# LEDController.net
KiCad netlist of a schematic drawn in EAGLE
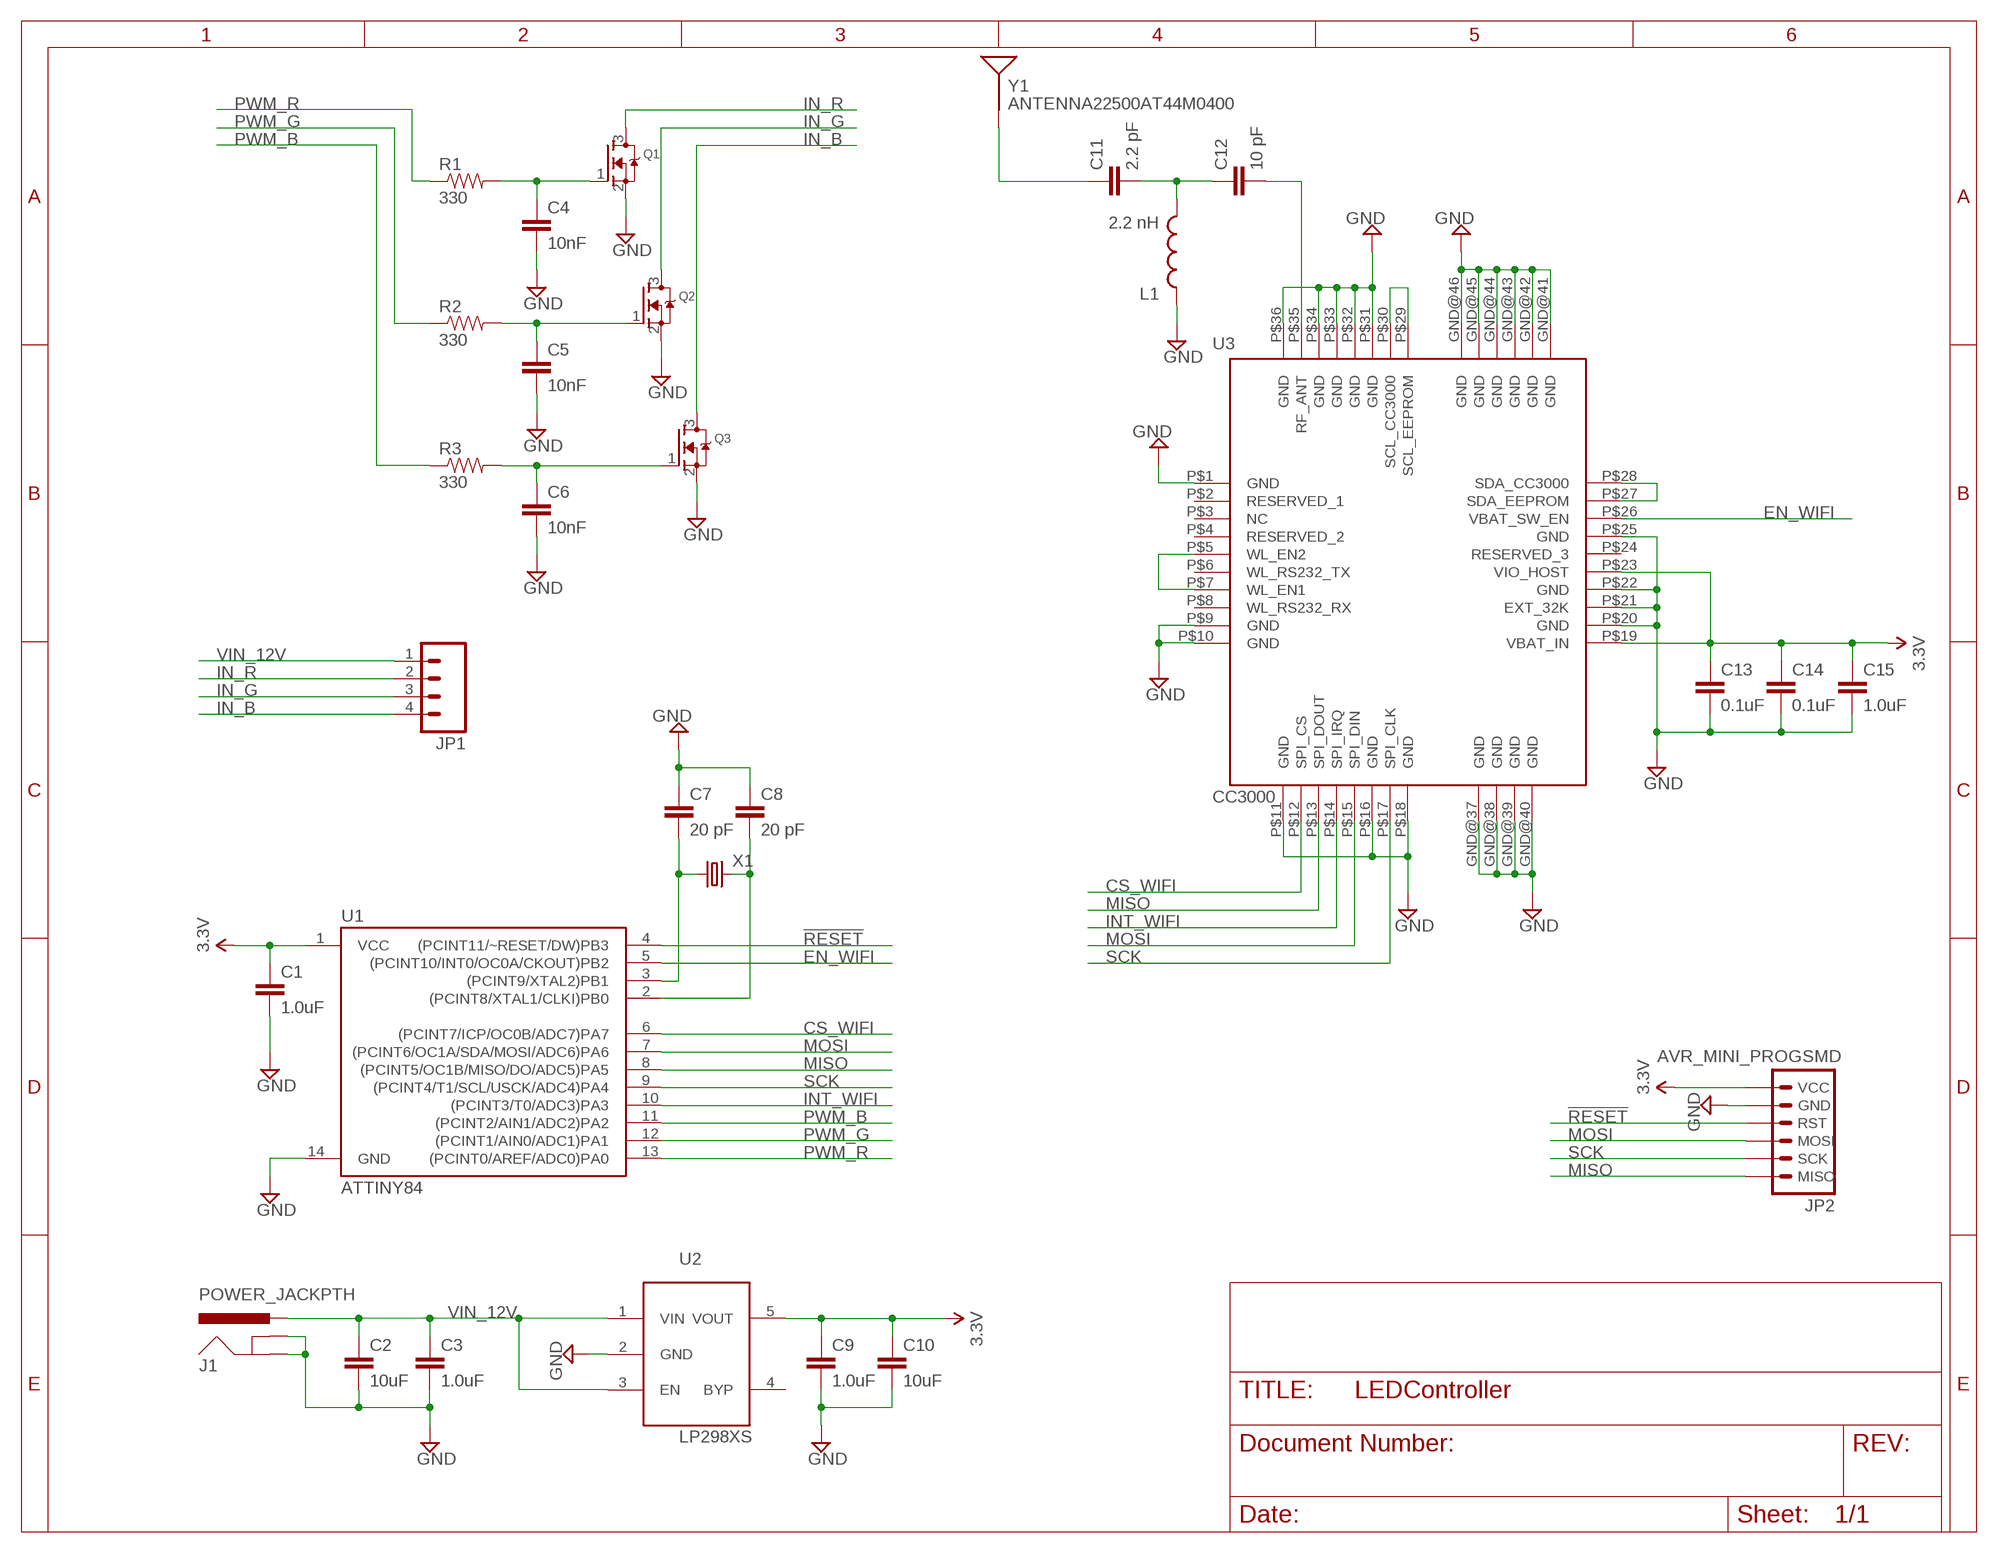
[diagram p0: schematic, sheet 1]

(export (version "E")
  (design (tool "Eeschema 10.0.6"))
  (components
    (comp (ref "C1")
      (value "1.0uF")
      (footprint "eagle-import:0603-CAP")
      (libsource (lib "eagle-import") (part "1.0UF-16V-10%(0603)"))
    )
    (comp (ref "C2")
      (value "10uF")
      (footprint "eagle-import:0603-CAP")
      (libsource (lib "eagle-import") (part "10UF-6.3V-20%(0603)"))
    )
    (comp (ref "C3")
      (value "1.0uF")
      (footprint "eagle-import:0603-CAP")
      (libsource (lib "eagle-import") (part "1.0UF-16V-10%(0603)"))
    )
    (comp (ref "C4")
      (value "10nF")
      (footprint "eagle-import:0603-CAP")
      (libsource (lib "eagle-import") (part "10NF/10000PF-50V-10%(0603)"))
    )
    (comp (ref "C5")
      (value "10nF")
      (footprint "eagle-import:0603-CAP")
      (libsource (lib "eagle-import") (part "10NF/10000PF-50V-10%(0603)"))
    )
    (comp (ref "C6")
      (value "10nF")
      (footprint "eagle-import:0603-CAP")
      (libsource (lib "eagle-import") (part "10NF/10000PF-50V-10%(0603)"))
    )
    (comp (ref "C7")
      (value "20 pF")
      (footprint "eagle-import:0603-CAP")
      (libsource (lib "eagle-import") (part "9.0PF-50V-10%(0603)"))
    )
    (comp (ref "C8")
      (value "20 pF")
      (footprint "eagle-import:0603-CAP")
      (libsource (lib "eagle-import") (part "9.0PF-50V-10%(0603)"))
    )
    (comp (ref "C9")
      (value "1.0uF")
      (footprint "eagle-import:0603-CAP")
      (libsource (lib "eagle-import") (part "1.0UF-16V-10%(0603)"))
    )
    (comp (ref "C10")
      (value "10uF")
      (footprint "eagle-import:0603-CAP")
      (libsource (lib "eagle-import") (part "10UF-6.3V-20%(0603)"))
    )
    (comp (ref "C11")
      (value "2.2 pF")
      (footprint "eagle-import:0603-CAP")
      (libsource (lib "eagle-import") (part "9.0PF-50V-10%(0603)"))
    )
    (comp (ref "C12")
      (value "10 pF")
      (footprint "eagle-import:0603-CAP")
      (libsource (lib "eagle-import") (part "9.0PF-50V-10%(0603)"))
    )
    (comp (ref "C13")
      (value "0.1uF")
      (footprint "eagle-import:0603-CAP")
      (libsource (lib "eagle-import") (part "0.1UF-25V-5%(0603)"))
    )
    (comp (ref "C14")
      (value "0.1uF")
      (footprint "eagle-import:0603-CAP")
      (libsource (lib "eagle-import") (part "0.1UF-25V-5%(0603)"))
    )
    (comp (ref "C15")
      (value "1.0uF")
      (footprint "eagle-import:0603-CAP")
      (libsource (lib "eagle-import") (part "1.0UF-16V-10%(0603)"))
    )
    (comp (ref "J1")
      (value "POWER_JACKPTH")
      (footprint "eagle-import:POWER_JACK_PTH")
      (libsource (lib "eagle-import") (part "POWER_JACKPTH"))
    )
    (comp (ref "JP1")
      (value "M04PTH")
      (footprint "eagle-import:1X04")
      (libsource (lib "eagle-import") (part "M04PTH"))
    )
    (comp (ref "JP2")
      (value "AVR_MINI_PROGSMD")
      (footprint "eagle-import:AVR_MINI_PROG")
      (libsource (lib "eagle-import") (part "AVR_MINI_PROGSMD"))
    )
    (comp (ref "L1")
      (value "2.2 nH")
      (footprint "eagle-import:0603")
      (libsource (lib "eagle-import") (part "INDUCTOR0603"))
    )
    (comp (ref "Q1")
      (value "MOSFET-NREFLOW")
      (footprint "eagle-import:SOT23")
      (libsource (lib "eagle-import") (part "MOSFET-NREFLOW"))
    )
    (comp (ref "Q2")
      (value "MOSFET-NREFLOW")
      (footprint "eagle-import:SOT23")
      (libsource (lib "eagle-import") (part "MOSFET-NREFLOW"))
    )
    (comp (ref "Q3")
      (value "MOSFET-NREFLOW")
      (footprint "eagle-import:SOT23")
      (libsource (lib "eagle-import") (part "MOSFET-NREFLOW"))
    )
    (comp (ref "R1")
      (value "330")
      (footprint "eagle-import:0603-RES")
      (libsource (lib "eagle-import") (part "330OHM1/10W1%(0603)"))
    )
    (comp (ref "R2")
      (value "330")
      (footprint "eagle-import:0603-RES")
      (libsource (lib "eagle-import") (part "330OHM1/10W1%(0603)"))
    )
    (comp (ref "R3")
      (value "330")
      (footprint "eagle-import:0603-RES")
      (libsource (lib "eagle-import") (part "330OHM1/10W1%(0603)"))
    )
    (comp (ref "U1")
      (value "ATTINY84")
      (footprint "eagle-import:SO14")
      (libsource (lib "eagle-import") (part "ATTINY84"))
    )
    (comp (ref "U2")
      (value "LP298XS")
      (footprint "eagle-import:SOT23-5L")
      (libsource (lib "eagle-import") (part "LP298XS"))
    )
    (comp (ref "U3")
      (value "CC3000")
      (footprint "eagle-import:QFN-46_CC3000")
      (libsource (lib "eagle-import") (part "CC3000"))
    )
    (comp (ref "X1")
      (value "CRYSTAL5X3")
      (footprint "eagle-import:CRYSTAL-SMD-5X3")
      (libsource (lib "eagle-import") (part "CRYSTAL5X3"))
    )
    (comp (ref "Y1")
      (value "ANTENNA22500AT44M0400")
      (footprint "eagle-import:ANTENNA-CHIP_2500AT44M0400")
      (libsource (lib "eagle-import") (part "ANTENNA22500AT44M0400"))
    )
  )
  (nets
    (net (code "1") (name "/CS_WIFI") (class "Default")
      (node (ref "U1") (pin "6") (pinfunction "(PCINT7/ICP/OC0B/ADC7)PA7_6") (pintype "bidirectional"))
      (node (ref "U3") (pin "P$12") (pinfunction "SPI_CS_P$12") (pintype "bidirectional"))
    )
    (net (code "2") (name "/EN_WIFI") (class "Default")
      (node (ref "U1") (pin "5") (pinfunction "(PCINT10/INT0/OC0A/CKOUT)PB2_5") (pintype "bidirectional"))
      (node (ref "U3") (pin "P$26") (pinfunction "VBAT_SW_EN_P$26") (pintype "bidirectional"))
    )
    (net (code "3") (name "/INT_WIFI") (class "Default")
      (node (ref "U1") (pin "10") (pinfunction "(PCINT3/T0/ADC3)PA3_10") (pintype "bidirectional"))
      (node (ref "U3") (pin "P$14") (pinfunction "SPI_IRQ_P$14") (pintype "bidirectional"))
    )
    (net (code "4") (name "/IN_B") (class "Default")
      (node (ref "JP1") (pin "4") (pinfunction "4_4") (pintype "passive"))
      (node (ref "Q3") (pin "3") (pinfunction "D_3") (pintype "bidirectional"))
    )
    (net (code "5") (name "/IN_G") (class "Default")
      (node (ref "JP1") (pin "3") (pinfunction "3_3") (pintype "passive"))
      (node (ref "Q2") (pin "3") (pinfunction "D_3") (pintype "bidirectional"))
    )
    (net (code "6") (name "/IN_R") (class "Default")
      (node (ref "JP1") (pin "2") (pinfunction "2_2") (pintype "passive"))
      (node (ref "Q1") (pin "3") (pinfunction "D_3") (pintype "bidirectional"))
    )
    (net (code "7") (name "/MISO") (class "Default")
      (node (ref "JP2") (pin "6") (pinfunction "MISO_6") (pintype "passive"))
      (node (ref "U1") (pin "8") (pinfunction "(PCINT5/OC1B/MISO/DO/ADC5)PA5_8") (pintype "bidirectional"))
      (node (ref "U3") (pin "P$13") (pinfunction "SPI_DOUT_P$13") (pintype "bidirectional"))
    )
    (net (code "8") (name "/MOSI") (class "Default")
      (node (ref "JP2") (pin "4") (pinfunction "MOSI_4") (pintype "passive"))
      (node (ref "U1") (pin "7") (pinfunction "(PCINT6/OC1A/SDA/MOSI/ADC6)PA6_7") (pintype "bidirectional"))
      (node (ref "U3") (pin "P$15") (pinfunction "SPI_DIN_P$15") (pintype "bidirectional"))
    )
    (net (code "9") (name "/PWM_B") (class "Default")
      (node (ref "R3") (pin "1") (pinfunction "1_1") (pintype "passive"))
      (node (ref "U1") (pin "11") (pinfunction "(PCINT2/AIN1/ADC2)PA2_11") (pintype "bidirectional"))
    )
    (net (code "10") (name "/PWM_G") (class "Default")
      (node (ref "R2") (pin "1") (pinfunction "1_1") (pintype "passive"))
      (node (ref "U1") (pin "12") (pinfunction "(PCINT1/AIN0/ADC1)PA1_12") (pintype "bidirectional"))
    )
    (net (code "11") (name "/PWM_R") (class "Default")
      (node (ref "R1") (pin "1") (pinfunction "1_1") (pintype "passive"))
      (node (ref "U1") (pin "13") (pinfunction "(PCINT0/AREF/ADC0)PA0_13") (pintype "bidirectional"))
    )
    (net (code "12") (name "/SCK") (class "Default")
      (node (ref "JP2") (pin "5") (pinfunction "SCK_5") (pintype "passive"))
      (node (ref "U1") (pin "9") (pinfunction "(PCINT4/T1/SCL/USCK/ADC4)PA4_9") (pintype "bidirectional"))
      (node (ref "U3") (pin "P$17") (pinfunction "SPI_CLK_P$17") (pintype "bidirectional"))
    )
    (net (code "13") (name "/VIN_12V") (class "Default")
      (node (ref "C2") (pin "1") (pinfunction "1_1") (pintype "passive"))
      (node (ref "C3") (pin "1") (pinfunction "1_1") (pintype "passive"))
      (node (ref "J1") (pin "PWR") (pinfunction "PWR_PWR") (pintype "bidirectional"))
      (node (ref "JP1") (pin "1") (pinfunction "1_1") (pintype "passive"))
      (node (ref "U2") (pin "1") (pinfunction "VIN_1") (pintype "bidirectional"))
      (node (ref "U2") (pin "3") (pinfunction "EN_3") (pintype "bidirectional"))
    )
    (net (code "14") (name "/~{RESET}") (class "Default")
      (node (ref "JP2") (pin "3") (pinfunction "RST_3") (pintype "passive"))
      (node (ref "U1") (pin "4") (pinfunction "(PCINT11/~{RESET/DW})PB3_4") (pintype "bidirectional"))
    )
    (net (code "15") (name "3.3V") (class "Default")
      (node (ref "C1") (pin "1") (pinfunction "1_1") (pintype "passive"))
      (node (ref "C10") (pin "1") (pinfunction "1_1") (pintype "passive"))
      (node (ref "C13") (pin "1") (pinfunction "1_1") (pintype "passive"))
      (node (ref "C14") (pin "1") (pinfunction "1_1") (pintype "passive"))
      (node (ref "C15") (pin "1") (pinfunction "1_1") (pintype "passive"))
      (node (ref "C9") (pin "1") (pinfunction "1_1") (pintype "passive"))
      (node (ref "JP2") (pin "1") (pinfunction "VCC_1") (pintype "passive"))
      (node (ref "U1") (pin "1") (pinfunction "VCC_1") (pintype "bidirectional"))
      (node (ref "U2") (pin "5") (pinfunction "VOUT_5") (pintype "bidirectional"))
      (node (ref "U3") (pin "P$19") (pinfunction "VBAT_IN_P$19") (pintype "bidirectional"))
      (node (ref "U3") (pin "P$23") (pinfunction "VIO_HOST_P$23") (pintype "bidirectional"))
    )
    (net (code "16") (name "GND") (class "Default")
      (node (ref "C1") (pin "2") (pinfunction "2_2") (pintype "passive"))
      (node (ref "C10") (pin "2") (pinfunction "2_2") (pintype "passive"))
      (node (ref "C13") (pin "2") (pinfunction "2_2") (pintype "passive"))
      (node (ref "C14") (pin "2") (pinfunction "2_2") (pintype "passive"))
      (node (ref "C15") (pin "2") (pinfunction "2_2") (pintype "passive"))
      (node (ref "C2") (pin "2") (pinfunction "2_2") (pintype "passive"))
      (node (ref "C3") (pin "2") (pinfunction "2_2") (pintype "passive"))
      (node (ref "C4") (pin "2") (pinfunction "2_2") (pintype "passive"))
      (node (ref "C5") (pin "2") (pinfunction "2_2") (pintype "passive"))
      (node (ref "C6") (pin "2") (pinfunction "2_2") (pintype "passive"))
      (node (ref "C7") (pin "1") (pinfunction "1_1") (pintype "passive"))
      (node (ref "C8") (pin "1") (pinfunction "1_1") (pintype "passive"))
      (node (ref "C9") (pin "2") (pinfunction "2_2") (pintype "passive"))
      (node (ref "J1") (pin "GND") (pinfunction "GND_GND") (pintype "bidirectional"))
      (node (ref "J1") (pin "GNDBREAK") (pinfunction "GNDBREAK_GNDBREAK") (pintype "bidirectional"))
      (node (ref "JP2") (pin "2") (pinfunction "GND_2") (pintype "passive"))
      (node (ref "L1") (pin "1") (pinfunction "1_1") (pintype "passive"))
      (node (ref "Q1") (pin "2") (pinfunction "S_2") (pintype "bidirectional"))
      (node (ref "Q2") (pin "2") (pinfunction "S_2") (pintype "bidirectional"))
      (node (ref "Q3") (pin "2") (pinfunction "S_2") (pintype "bidirectional"))
      (node (ref "U1") (pin "14") (pinfunction "GND_14") (pintype "bidirectional"))
      (node (ref "U2") (pin "2") (pinfunction "GND_2") (pintype "bidirectional"))
      (node (ref "U3") (pin "GND@37") (pinfunction "GND_GND@37") (pintype "bidirectional"))
      (node (ref "U3") (pin "GND@38") (pinfunction "GND_GND@38") (pintype "bidirectional"))
      (node (ref "U3") (pin "GND@39") (pinfunction "GND_GND@39") (pintype "bidirectional"))
      (node (ref "U3") (pin "GND@40") (pinfunction "GND_GND@40") (pintype "bidirectional"))
      (node (ref "U3") (pin "GND@41") (pinfunction "GND_GND@41") (pintype "bidirectional"))
      (node (ref "U3") (pin "GND@42") (pinfunction "GND_GND@42") (pintype "bidirectional"))
      (node (ref "U3") (pin "GND@43") (pinfunction "GND_GND@43") (pintype "bidirectional"))
      (node (ref "U3") (pin "GND@44") (pinfunction "GND_GND@44") (pintype "bidirectional"))
      (node (ref "U3") (pin "GND@45") (pinfunction "GND_GND@45") (pintype "bidirectional"))
      (node (ref "U3") (pin "GND@46") (pinfunction "GND_GND@46") (pintype "bidirectional"))
      (node (ref "U3") (pin "P$1") (pinfunction "GND_P$1") (pintype "bidirectional"))
      (node (ref "U3") (pin "P$10") (pinfunction "GND_P$10") (pintype "bidirectional"))
      (node (ref "U3") (pin "P$11") (pinfunction "GND_P$11") (pintype "bidirectional"))
      (node (ref "U3") (pin "P$16") (pinfunction "GND_P$16") (pintype "bidirectional"))
      (node (ref "U3") (pin "P$18") (pinfunction "GND_P$18") (pintype "bidirectional"))
      (node (ref "U3") (pin "P$20") (pinfunction "GND_P$20") (pintype "bidirectional"))
      (node (ref "U3") (pin "P$21") (pinfunction "EXT_32K_P$21") (pintype "bidirectional"))
      (node (ref "U3") (pin "P$22") (pinfunction "GND_P$22") (pintype "bidirectional"))
      (node (ref "U3") (pin "P$25") (pinfunction "GND_P$25") (pintype "bidirectional"))
      (node (ref "U3") (pin "P$31") (pinfunction "GND_P$31") (pintype "bidirectional"))
      (node (ref "U3") (pin "P$32") (pinfunction "GND_P$32") (pintype "bidirectional"))
      (node (ref "U3") (pin "P$33") (pinfunction "GND_P$33") (pintype "bidirectional"))
      (node (ref "U3") (pin "P$34") (pinfunction "GND_P$34") (pintype "bidirectional"))
      (node (ref "U3") (pin "P$36") (pinfunction "GND_P$36") (pintype "bidirectional"))
      (node (ref "U3") (pin "P$9") (pinfunction "GND_P$9") (pintype "bidirectional"))
    )
    (net (code "17") (name "Net-(C11-Pad2)") (class "Default")
      (node (ref "C11") (pin "2") (pinfunction "2_2") (pintype "passive"))
      (node (ref "C12") (pin "1") (pinfunction "1_1") (pintype "passive"))
      (node (ref "L1") (pin "2") (pinfunction "2_2") (pintype "passive"))
    )
    (net (code "18") (name "Net-(Q1-G)") (class "Default")
      (node (ref "C4") (pin "1") (pinfunction "1_1") (pintype "passive"))
      (node (ref "Q1") (pin "1") (pinfunction "G_1") (pintype "bidirectional"))
      (node (ref "R1") (pin "2") (pinfunction "2_2") (pintype "passive"))
    )
    (net (code "19") (name "Net-(Q2-G)") (class "Default")
      (node (ref "C5") (pin "1") (pinfunction "1_1") (pintype "passive"))
      (node (ref "Q2") (pin "1") (pinfunction "G_1") (pintype "bidirectional"))
      (node (ref "R2") (pin "2") (pinfunction "2_2") (pintype "passive"))
    )
    (net (code "20") (name "Net-(Q3-G)") (class "Default")
      (node (ref "C6") (pin "1") (pinfunction "1_1") (pintype "passive"))
      (node (ref "Q3") (pin "1") (pinfunction "G_1") (pintype "bidirectional"))
      (node (ref "R3") (pin "2") (pinfunction "2_2") (pintype "passive"))
    )
    (net (code "21") (name "Net-(U1-(PCINT8{slash}XTAL1{slash}CLKI)PB0)") (class "Default")
      (node (ref "C8") (pin "2") (pinfunction "2_2") (pintype "passive"))
      (node (ref "U1") (pin "2") (pinfunction "(PCINT8/XTAL1/CLKI)PB0_2") (pintype "bidirectional"))
      (node (ref "X1") (pin "3") (pinfunction "2_3") (pintype "passive"))
    )
    (net (code "22") (name "Net-(U1-(PCINT9{slash}XTAL2)PB1)") (class "Default")
      (node (ref "C7") (pin "2") (pinfunction "2_2") (pintype "passive"))
      (node (ref "U1") (pin "3") (pinfunction "(PCINT9/XTAL2)PB1_3") (pintype "bidirectional"))
      (node (ref "X1") (pin "1") (pinfunction "1_1") (pintype "passive"))
    )
    (net (code "23") (name "Net-(U3-RF_ANT)") (class "Default")
      (node (ref "C12") (pin "2") (pinfunction "2_2") (pintype "passive"))
      (node (ref "U3") (pin "P$35") (pinfunction "RF_ANT_P$35") (pintype "bidirectional"))
    )
    (net (code "24") (name "Net-(U3-SCL_CC3000)") (class "Default")
      (node (ref "U3") (pin "P$29") (pinfunction "SCL_EEPROM_P$29") (pintype "bidirectional"))
      (node (ref "U3") (pin "P$30") (pinfunction "SCL_CC3000_P$30") (pintype "bidirectional"))
    )
    (net (code "25") (name "Net-(U3-SDA_CC3000)") (class "Default")
      (node (ref "U3") (pin "P$27") (pinfunction "SDA_EEPROM_P$27") (pintype "bidirectional"))
      (node (ref "U3") (pin "P$28") (pinfunction "SDA_CC3000_P$28") (pintype "bidirectional"))
    )
    (net (code "26") (name "Net-(U3-WL_EN1)") (class "Default")
      (node (ref "U3") (pin "P$5") (pinfunction "WL_EN2_P$5") (pintype "bidirectional"))
      (node (ref "U3") (pin "P$7") (pinfunction "WL_EN1_P$7") (pintype "bidirectional"))
    )
    (net (code "27") (name "Net-(Y1-SIGNAL)") (class "Default")
      (node (ref "C11") (pin "1") (pinfunction "1_1") (pintype "passive"))
      (node (ref "Y1") (pin "FEED") (pinfunction "SIGNAL_FEED") (pintype "bidirectional"))
    )
    (net (code "28") (name "unconnected-(U2-BYP-Pad4)") (class "Default")
      (node (ref "U2") (pin "4") (pinfunction "BYP_4") (pintype "bidirectional"))
    )
    (net (code "29") (name "unconnected-(U3-NC-PadP$3)") (class "Default")
      (node (ref "U3") (pin "P$3") (pinfunction "NC_P$3") (pintype "bidirectional"))
    )
    (net (code "30") (name "unconnected-(U3-RESERVED_1-PadP$2)") (class "Default")
      (node (ref "U3") (pin "P$2") (pinfunction "RESERVED_1_P$2") (pintype "bidirectional"))
    )
    (net (code "31") (name "unconnected-(U3-RESERVED_2-PadP$4)") (class "Default")
      (node (ref "U3") (pin "P$4") (pinfunction "RESERVED_2_P$4") (pintype "bidirectional"))
    )
    (net (code "32") (name "unconnected-(U3-RESERVED_3-PadP$24)") (class "Default")
      (node (ref "U3") (pin "P$24") (pinfunction "RESERVED_3_P$24") (pintype "bidirectional"))
    )
    (net (code "33") (name "unconnected-(U3-WL_RS232_RX-PadP$8)") (class "Default")
      (node (ref "U3") (pin "P$8") (pinfunction "WL_RS232_RX_P$8") (pintype "bidirectional"))
    )
    (net (code "34") (name "unconnected-(U3-WL_RS232_TX-PadP$6)") (class "Default")
      (node (ref "U3") (pin "P$6") (pinfunction "WL_RS232_TX_P$6") (pintype "bidirectional"))
    )
  )
)
